# design.net
KiCad netlist of a schematic drawn in Altium Designer
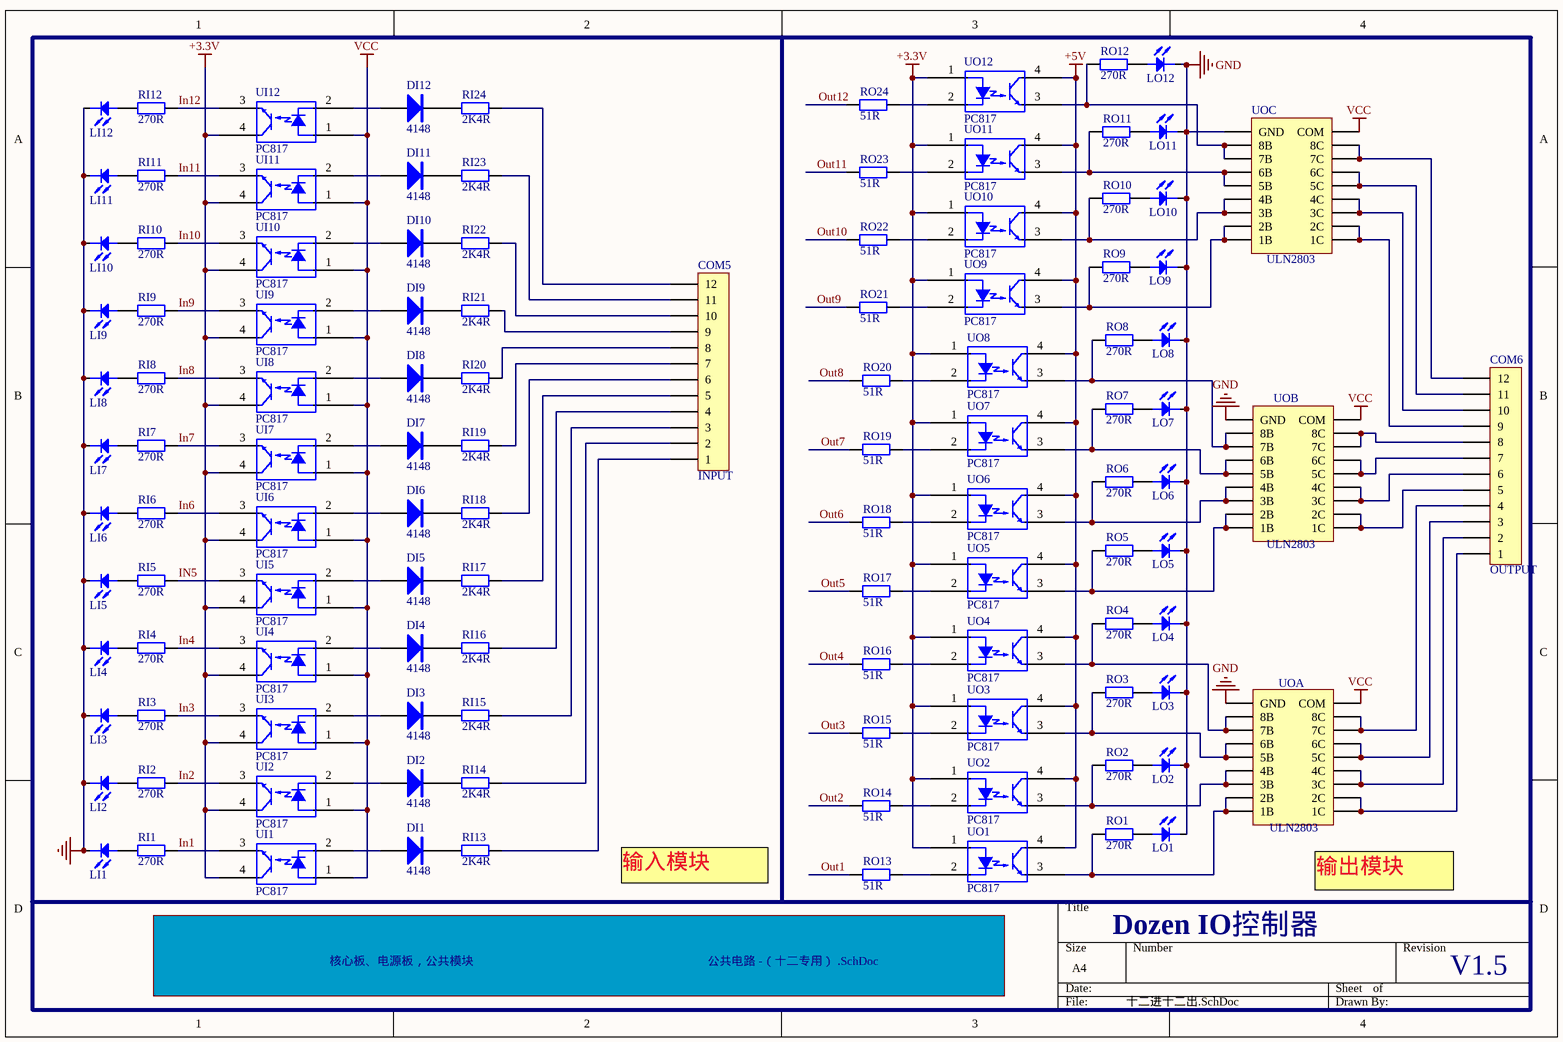
[diagram p0: 十二进十二出.SchDoc]

(export (version "E")
  (design (tool "Eeschema 10.0.6"))
  (components
    (comp (ref "COM5") (value "INPUT") (footprint "CON12-5.1卧上") (libsource (lib "阿波罗") (part "CON12")))
    (comp (ref "COM6") (value "OUTPUT") (footprint "CON12-5.1卧下") (libsource (lib "阿波罗") (part "CON12")))
    (comp (ref "DI1")
      (value "4148")
      (footprint "1206C")
      (libsource (lib "altium-import") (part "root_0__阿波罗.SCHLIB"))
    )
    (comp (ref "DI2")
      (value "4148")
      (footprint "1206C")
      (libsource (lib "altium-import") (part "root_0__阿波罗.SCHLIB"))
    )
    (comp (ref "DI3")
      (value "4148")
      (footprint "1206C")
      (libsource (lib "altium-import") (part "root_0__阿波罗.SCHLIB"))
    )
    (comp (ref "DI4")
      (value "4148")
      (footprint "1206C")
      (libsource (lib "altium-import") (part "root_0__阿波罗.SCHLIB"))
    )
    (comp (ref "DI5")
      (value "4148")
      (footprint "1206C")
      (libsource (lib "altium-import") (part "root_0__阿波罗.SCHLIB"))
    )
    (comp (ref "DI6")
      (value "4148")
      (footprint "1206C")
      (libsource (lib "altium-import") (part "root_0__阿波罗.SCHLIB"))
    )
    (comp (ref "DI7")
      (value "4148")
      (footprint "1206C")
      (libsource (lib "altium-import") (part "root_0__阿波罗.SCHLIB"))
    )
    (comp (ref "DI8")
      (value "4148")
      (footprint "1206C")
      (libsource (lib "altium-import") (part "root_0__阿波罗.SCHLIB"))
    )
    (comp (ref "DI9")
      (value "4148")
      (footprint "1206C")
      (libsource (lib "altium-import") (part "root_0__阿波罗.SCHLIB"))
    )
    (comp (ref "DI10")
      (value "4148")
      (footprint "1206C")
      (libsource (lib "altium-import") (part "root_0__阿波罗.SCHLIB"))
    )
    (comp (ref "DI11")
      (value "4148")
      (footprint "1206C")
      (libsource (lib "altium-import") (part "root_0__阿波罗.SCHLIB"))
    )
    (comp (ref "DI12")
      (value "4148")
      (footprint "1206C")
      (libsource (lib "altium-import") (part "root_0__阿波罗.SCHLIB"))
    )
    (comp (ref "LI1") (value "LED") (footprint "SMDLED") (libsource (lib "*") (part "LED")))
    (comp (ref "LI2") (value "LED") (footprint "SMDLED") (libsource (lib "*") (part "LED")))
    (comp (ref "LI3") (value "LED") (footprint "SMDLED") (libsource (lib "*") (part "LED")))
    (comp (ref "LI4") (value "LED") (footprint "SMDLED") (libsource (lib "*") (part "LED")))
    (comp (ref "LI5") (value "LED") (footprint "SMDLED") (libsource (lib "*") (part "LED")))
    (comp (ref "LI6") (value "LED") (footprint "SMDLED") (libsource (lib "*") (part "LED")))
    (comp (ref "LI7") (value "LED") (footprint "SMDLED") (libsource (lib "*") (part "LED")))
    (comp (ref "LI8") (value "LED") (footprint "SMDLED") (libsource (lib "*") (part "LED")))
    (comp (ref "LI9") (value "LED") (footprint "SMDLED") (libsource (lib "*") (part "LED")))
    (comp (ref "LI10") (value "LED") (footprint "SMDLED") (libsource (lib "*") (part "LED")))
    (comp (ref "LI11") (value "LED") (footprint "SMDLED") (libsource (lib "*") (part "LED")))
    (comp (ref "LI12") (value "LED") (footprint "SMDLED") (libsource (lib "*") (part "LED")))
    (comp (ref "LO1") (value "LED") (footprint "SMDLED") (libsource (lib "*") (part "LED")))
    (comp (ref "LO2") (value "LED") (footprint "SMDLED") (libsource (lib "*") (part "LED")))
    (comp (ref "LO3") (value "LED") (footprint "SMDLED") (libsource (lib "*") (part "LED")))
    (comp (ref "LO4") (value "LED") (footprint "SMDLED") (libsource (lib "*") (part "LED")))
    (comp (ref "LO5") (value "LED") (footprint "SMDLED") (libsource (lib "*") (part "LED")))
    (comp (ref "LO6") (value "LED") (footprint "SMDLED") (libsource (lib "*") (part "LED")))
    (comp (ref "LO7") (value "LED") (footprint "SMDLED") (libsource (lib "*") (part "LED")))
    (comp (ref "LO8") (value "LED") (footprint "SMDLED") (libsource (lib "*") (part "LED")))
    (comp (ref "LO9") (value "LED") (footprint "SMDLED") (libsource (lib "*") (part "LED")))
    (comp (ref "LO10") (value "LED") (footprint "SMDLED") (libsource (lib "*") (part "LED")))
    (comp (ref "LO11") (value "LED") (footprint "SMDLED") (libsource (lib "*") (part "LED")))
    (comp (ref "LO12") (value "LED") (footprint "SMDLED") (libsource (lib "*") (part "LED")))
    (comp (ref "RI1")
      (value "270R")
      (footprint "0603A")
      (description "Resistor")
      (fields (field (name "PUBLISHER") "Altium Limited"))
      (libsource (lib "") (part "Res2_1"))
    )
    (comp (ref "RI2")
      (value "270R")
      (footprint "0603A")
      (description "Resistor")
      (fields (field (name "PUBLISHER") "Altium Limited"))
      (libsource (lib "") (part "Res2_1"))
    )
    (comp (ref "RI3")
      (value "270R")
      (footprint "0603A")
      (description "Resistor")
      (fields (field (name "PUBLISHER") "Altium Limited"))
      (libsource (lib "") (part "Res2_1"))
    )
    (comp (ref "RI4")
      (value "270R")
      (footprint "0603A")
      (description "Resistor")
      (fields (field (name "PUBLISHER") "Altium Limited"))
      (libsource (lib "") (part "Res2_1"))
    )
    (comp (ref "RI5")
      (value "270R")
      (footprint "0603A")
      (description "Resistor")
      (fields (field (name "PUBLISHER") "Altium Limited"))
      (libsource (lib "") (part "Res2_1"))
    )
    (comp (ref "RI6")
      (value "270R")
      (footprint "0603A")
      (description "Resistor")
      (fields (field (name "PUBLISHER") "Altium Limited"))
      (libsource (lib "") (part "Res2_1"))
    )
    (comp (ref "RI7")
      (value "270R")
      (footprint "0603A")
      (description "Resistor")
      (fields (field (name "PUBLISHER") "Altium Limited"))
      (libsource (lib "") (part "Res2_1"))
    )
    (comp (ref "RI8")
      (value "270R")
      (footprint "0603A")
      (description "Resistor")
      (fields (field (name "PUBLISHER") "Altium Limited"))
      (libsource (lib "") (part "Res2_1"))
    )
    (comp (ref "RI9")
      (value "270R")
      (footprint "0603A")
      (description "Resistor")
      (fields (field (name "PUBLISHER") "Altium Limited"))
      (libsource (lib "") (part "Res2_1"))
    )
    (comp (ref "RI10")
      (value "270R")
      (footprint "0603A")
      (description "Resistor")
      (fields (field (name "PUBLISHER") "Altium Limited"))
      (libsource (lib "") (part "Res2_1"))
    )
    (comp (ref "RI11")
      (value "270R")
      (footprint "0603A")
      (description "Resistor")
      (fields (field (name "PUBLISHER") "Altium Limited"))
      (libsource (lib "") (part "Res2_1"))
    )
    (comp (ref "RI12")
      (value "270R")
      (footprint "0603A")
      (description "Resistor")
      (fields (field (name "PUBLISHER") "Altium Limited"))
      (libsource (lib "") (part "Res2_1"))
    )
    (comp (ref "RI13")
      (value "2K4R")
      (footprint "0603A")
      (description "Resistor")
      (fields (field (name "PUBLISHER") "Altium Limited"))
      (libsource (lib "*") (part "Res2"))
    )
    (comp (ref "RI14")
      (value "2K4R")
      (footprint "0603A")
      (description "Resistor")
      (fields (field (name "PUBLISHER") "Altium Limited"))
      (libsource (lib "*") (part "Res2"))
    )
    (comp (ref "RI15")
      (value "2K4R")
      (footprint "0603A")
      (description "Resistor")
      (fields (field (name "PUBLISHER") "Altium Limited"))
      (libsource (lib "*") (part "Res2"))
    )
    (comp (ref "RI16")
      (value "2K4R")
      (footprint "0603A")
      (description "Resistor")
      (fields (field (name "PUBLISHER") "Altium Limited"))
      (libsource (lib "*") (part "Res2"))
    )
    (comp (ref "RI17")
      (value "2K4R")
      (footprint "0603A")
      (description "Resistor")
      (fields (field (name "PUBLISHER") "Altium Limited"))
      (libsource (lib "*") (part "Res2"))
    )
    (comp (ref "RI18")
      (value "2K4R")
      (footprint "0603A")
      (description "Resistor")
      (fields (field (name "PUBLISHER") "Altium Limited"))
      (libsource (lib "*") (part "Res2"))
    )
    (comp (ref "RI19")
      (value "2K4R")
      (footprint "0603A")
      (description "Resistor")
      (fields (field (name "PUBLISHER") "Altium Limited"))
      (libsource (lib "*") (part "Res2"))
    )
    (comp (ref "RI20")
      (value "2K4R")
      (footprint "0603A")
      (description "Resistor")
      (fields (field (name "PUBLISHER") "Altium Limited"))
      (libsource (lib "*") (part "Res2"))
    )
    (comp (ref "RI21")
      (value "2K4R")
      (footprint "0603A")
      (description "Resistor")
      (fields (field (name "PUBLISHER") "Altium Limited"))
      (libsource (lib "*") (part "Res2"))
    )
    (comp (ref "RI22")
      (value "2K4R")
      (footprint "0603A")
      (description "Resistor")
      (fields (field (name "PUBLISHER") "Altium Limited"))
      (libsource (lib "*") (part "Res2"))
    )
    (comp (ref "RI23")
      (value "2K4R")
      (footprint "0603A")
      (description "Resistor")
      (fields (field (name "PUBLISHER") "Altium Limited"))
      (libsource (lib "*") (part "Res2"))
    )
    (comp (ref "RI24")
      (value "2K4R")
      (footprint "0603A")
      (description "Resistor")
      (fields (field (name "PUBLISHER") "Altium Limited"))
      (libsource (lib "*") (part "Res2"))
    )
    (comp (ref "RO1")
      (value "270R")
      (footprint "0603A")
      (description "Resistor")
      (fields (field (name "PUBLISHER") "Altium Limited"))
      (libsource (lib "*") (part "Res2"))
    )
    (comp (ref "RO2")
      (value "270R")
      (footprint "0603A")
      (description "Resistor")
      (fields (field (name "PUBLISHER") "Altium Limited"))
      (libsource (lib "*") (part "Res2"))
    )
    (comp (ref "RO3")
      (value "270R")
      (footprint "0603A")
      (description "Resistor")
      (fields (field (name "PUBLISHER") "Altium Limited"))
      (libsource (lib "*") (part "Res2"))
    )
    (comp (ref "RO4")
      (value "270R")
      (footprint "0603A")
      (description "Resistor")
      (fields (field (name "PUBLISHER") "Altium Limited"))
      (libsource (lib "*") (part "Res2"))
    )
    (comp (ref "RO5")
      (value "270R")
      (footprint "0603A")
      (description "Resistor")
      (fields (field (name "PUBLISHER") "Altium Limited"))
      (libsource (lib "*") (part "Res2"))
    )
    (comp (ref "RO6")
      (value "270R")
      (footprint "0603A")
      (description "Resistor")
      (fields (field (name "PUBLISHER") "Altium Limited"))
      (libsource (lib "*") (part "Res2"))
    )
    (comp (ref "RO7")
      (value "270R")
      (footprint "0603A")
      (description "Resistor")
      (fields (field (name "PUBLISHER") "Altium Limited"))
      (libsource (lib "*") (part "Res2"))
    )
    (comp (ref "RO8")
      (value "270R")
      (footprint "0603A")
      (description "Resistor")
      (fields (field (name "PUBLISHER") "Altium Limited"))
      (libsource (lib "*") (part "Res2"))
    )
    (comp (ref "RO9")
      (value "270R")
      (footprint "0603A")
      (description "Resistor")
      (fields (field (name "PUBLISHER") "Altium Limited"))
      (libsource (lib "*") (part "Res2"))
    )
    (comp (ref "RO10")
      (value "270R")
      (footprint "0603A")
      (description "Resistor")
      (fields (field (name "PUBLISHER") "Altium Limited"))
      (libsource (lib "*") (part "Res2"))
    )
    (comp (ref "RO11")
      (value "270R")
      (footprint "0603A")
      (description "Resistor")
      (fields (field (name "PUBLISHER") "Altium Limited"))
      (libsource (lib "*") (part "Res2"))
    )
    (comp (ref "RO12")
      (value "270R")
      (footprint "0603A")
      (description "Resistor")
      (fields (field (name "PUBLISHER") "Altium Limited"))
      (libsource (lib "*") (part "Res2"))
    )
    (comp (ref "RO13")
      (value "51R")
      (footprint "0603A")
      (description "Resistor")
      (fields (field (name "PUBLISHER") "Altium Limited"))
      (libsource (lib "*") (part "Res2"))
    )
    (comp (ref "RO14")
      (value "51R")
      (footprint "0603A")
      (description "Resistor")
      (fields (field (name "PUBLISHER") "Altium Limited"))
      (libsource (lib "*") (part "Res2"))
    )
    (comp (ref "RO15")
      (value "51R")
      (footprint "0603A")
      (description "Resistor")
      (fields (field (name "PUBLISHER") "Altium Limited"))
      (libsource (lib "*") (part "Res2"))
    )
    (comp (ref "RO16")
      (value "51R")
      (footprint "0603A")
      (description "Resistor")
      (fields (field (name "PUBLISHER") "Altium Limited"))
      (libsource (lib "*") (part "Res2"))
    )
    (comp (ref "RO17")
      (value "51R")
      (footprint "0603A")
      (description "Resistor")
      (fields (field (name "PUBLISHER") "Altium Limited"))
      (libsource (lib "*") (part "Res2"))
    )
    (comp (ref "RO18")
      (value "51R")
      (footprint "0603A")
      (description "Resistor")
      (fields (field (name "PUBLISHER") "Altium Limited"))
      (libsource (lib "*") (part "Res2"))
    )
    (comp (ref "RO19")
      (value "51R")
      (footprint "0603A")
      (description "Resistor")
      (fields (field (name "PUBLISHER") "Altium Limited"))
      (libsource (lib "*") (part "Res2"))
    )
    (comp (ref "RO20")
      (value "51R")
      (footprint "0603A")
      (description "Resistor")
      (fields (field (name "PUBLISHER") "Altium Limited"))
      (libsource (lib "*") (part "Res2"))
    )
    (comp (ref "RO21")
      (value "51R")
      (footprint "0603A")
      (description "Resistor")
      (fields (field (name "PUBLISHER") "Altium Limited"))
      (libsource (lib "*") (part "Res2"))
    )
    (comp (ref "RO22")
      (value "51R")
      (footprint "0603A")
      (description "Resistor")
      (fields (field (name "PUBLISHER") "Altium Limited"))
      (libsource (lib "*") (part "Res2"))
    )
    (comp (ref "RO23")
      (value "51R")
      (footprint "0603A")
      (description "Resistor")
      (fields (field (name "PUBLISHER") "Altium Limited"))
      (libsource (lib "*") (part "Res2"))
    )
    (comp (ref "RO24")
      (value "51R")
      (footprint "0603A")
      (description "Resistor")
      (fields (field (name "PUBLISHER") "Altium Limited"))
      (libsource (lib "*") (part "Res2"))
    )
    (comp (ref "UI1")
      (value "PC817")
      (footprint "PC817")
      (description "Single NPN PhotoTransistor OptoCoupler.")
      (libsource (lib "*") (part "TLP521-1"))
    )
    (comp (ref "UI2")
      (value "PC817")
      (footprint "PC817")
      (description "Single NPN PhotoTransistor OptoCoupler.")
      (libsource (lib "*") (part "TLP521-1"))
    )
    (comp (ref "UI3")
      (value "PC817")
      (footprint "PC817")
      (description "Single NPN PhotoTransistor OptoCoupler.")
      (libsource (lib "*") (part "TLP521-1"))
    )
    (comp (ref "UI4")
      (value "PC817")
      (footprint "PC817")
      (description "Single NPN PhotoTransistor OptoCoupler.")
      (libsource (lib "*") (part "TLP521-1"))
    )
    (comp (ref "UI5")
      (value "PC817")
      (footprint "PC817")
      (description "Single NPN PhotoTransistor OptoCoupler.")
      (libsource (lib "*") (part "TLP521-1"))
    )
    (comp (ref "UI6")
      (value "PC817")
      (footprint "PC817")
      (description "Single NPN PhotoTransistor OptoCoupler.")
      (libsource (lib "*") (part "TLP521-1"))
    )
    (comp (ref "UI7")
      (value "PC817")
      (footprint "PC817")
      (description "Single NPN PhotoTransistor OptoCoupler.")
      (libsource (lib "*") (part "TLP521-1"))
    )
    (comp (ref "UI8")
      (value "PC817")
      (footprint "PC817")
      (description "Single NPN PhotoTransistor OptoCoupler.")
      (libsource (lib "*") (part "TLP521-1"))
    )
    (comp (ref "UI9")
      (value "PC817")
      (footprint "PC817")
      (description "Single NPN PhotoTransistor OptoCoupler.")
      (libsource (lib "*") (part "TLP521-1"))
    )
    (comp (ref "UI10")
      (value "PC817")
      (footprint "PC817")
      (description "Single NPN PhotoTransistor OptoCoupler.")
      (libsource (lib "*") (part "TLP521-1"))
    )
    (comp (ref "UI11")
      (value "PC817")
      (footprint "PC817")
      (description "Single NPN PhotoTransistor OptoCoupler.")
      (libsource (lib "*") (part "TLP521-1"))
    )
    (comp (ref "UI12")
      (value "PC817")
      (footprint "PC817")
      (description "Single NPN PhotoTransistor OptoCoupler.")
      (libsource (lib "*") (part "TLP521-1"))
    )
    (comp (ref "UO1")
      (value "PC817")
      (footprint "PC817")
      (description "Single NPN PhotoTransistor OptoCoupler.")
      (libsource (lib "*") (part "TLP521-1"))
    )
    (comp (ref "UO2")
      (value "PC817")
      (footprint "PC817")
      (description "Single NPN PhotoTransistor OptoCoupler.")
      (libsource (lib "*") (part "TLP521-1"))
    )
    (comp (ref "UO3")
      (value "PC817")
      (footprint "PC817")
      (description "Single NPN PhotoTransistor OptoCoupler.")
      (libsource (lib "*") (part "TLP521-1"))
    )
    (comp (ref "UO4")
      (value "PC817")
      (footprint "PC817")
      (description "Single NPN PhotoTransistor OptoCoupler.")
      (libsource (lib "*") (part "TLP521-1"))
    )
    (comp (ref "UO5")
      (value "PC817")
      (footprint "PC817")
      (description "Single NPN PhotoTransistor OptoCoupler.")
      (libsource (lib "*") (part "TLP521-1"))
    )
    (comp (ref "UO6")
      (value "PC817")
      (footprint "PC817")
      (description "Single NPN PhotoTransistor OptoCoupler.")
      (libsource (lib "*") (part "TLP521-1"))
    )
    (comp (ref "UO7")
      (value "PC817")
      (footprint "PC817")
      (description "Single NPN PhotoTransistor OptoCoupler.")
      (libsource (lib "*") (part "TLP521-1"))
    )
    (comp (ref "UO8")
      (value "PC817")
      (footprint "PC817")
      (description "Single NPN PhotoTransistor OptoCoupler.")
      (libsource (lib "*") (part "TLP521-1"))
    )
    (comp (ref "UO9")
      (value "PC817")
      (footprint "PC817")
      (description "Single NPN PhotoTransistor OptoCoupler.")
      (libsource (lib "*") (part "TLP521-1"))
    )
    (comp (ref "UO10")
      (value "PC817")
      (footprint "PC817")
      (description "Single NPN PhotoTransistor OptoCoupler.")
      (libsource (lib "*") (part "TLP521-1"))
    )
    (comp (ref "UO11")
      (value "PC817")
      (footprint "PC817")
      (description "Single NPN PhotoTransistor OptoCoupler.")
      (libsource (lib "*") (part "TLP521-1"))
    )
    (comp (ref "UO12")
      (value "PC817")
      (footprint "PC817")
      (description "Single NPN PhotoTransistor OptoCoupler.")
      (libsource (lib "*") (part "TLP521-1"))
    )
    (comp (ref "UOA") (value "ULN2803") (footprint "sol18") (libsource (lib "*") (part "ULN2803")))
    (comp (ref "UOB") (value "ULN2803") (footprint "sol18") (libsource (lib "*") (part "ULN2803")))
    (comp (ref "UOC") (value "ULN2803") (footprint "sol18") (libsource (lib "*") (part "ULN2803")))
  )
  (nets
    (net (code "1") (name "+3.3V") (class "Default")
      (node (ref "UI1") (pin "4") (pinfunction "COL_4") (pintype "passive"))
      (node (ref "UI10") (pin "4") (pinfunction "COL_4") (pintype "passive"))
      (node (ref "UI11") (pin "4") (pinfunction "COL_4") (pintype "passive"))
      (node (ref "UI12") (pin "4") (pinfunction "COL_4") (pintype "passive"))
      (node (ref "UI2") (pin "4") (pinfunction "COL_4") (pintype "passive"))
      (node (ref "UI3") (pin "4") (pinfunction "COL_4") (pintype "passive"))
      (node (ref "UI4") (pin "4") (pinfunction "COL_4") (pintype "passive"))
      (node (ref "UI5") (pin "4") (pinfunction "COL_4") (pintype "passive"))
      (node (ref "UI6") (pin "4") (pinfunction "COL_4") (pintype "passive"))
      (node (ref "UI7") (pin "4") (pinfunction "COL_4") (pintype "passive"))
      (node (ref "UI8") (pin "4") (pinfunction "COL_4") (pintype "passive"))
      (node (ref "UI9") (pin "4") (pinfunction "COL_4") (pintype "passive"))
      (node (ref "UO1") (pin "1") (pinfunction "ANODE_1") (pintype "passive"))
      (node (ref "UO10") (pin "1") (pinfunction "ANODE_1") (pintype "passive"))
      (node (ref "UO11") (pin "1") (pinfunction "ANODE_1") (pintype "passive"))
      (node (ref "UO12") (pin "1") (pinfunction "ANODE_1") (pintype "passive"))
      (node (ref "UO2") (pin "1") (pinfunction "ANODE_1") (pintype "passive"))
      (node (ref "UO3") (pin "1") (pinfunction "ANODE_1") (pintype "passive"))
      (node (ref "UO4") (pin "1") (pinfunction "ANODE_1") (pintype "passive"))
      (node (ref "UO5") (pin "1") (pinfunction "ANODE_1") (pintype "passive"))
      (node (ref "UO6") (pin "1") (pinfunction "ANODE_1") (pintype "passive"))
      (node (ref "UO7") (pin "1") (pinfunction "ANODE_1") (pintype "passive"))
      (node (ref "UO8") (pin "1") (pinfunction "ANODE_1") (pintype "passive"))
      (node (ref "UO9") (pin "1") (pinfunction "ANODE_1") (pintype "passive"))
    )
    (net (code "2") (name "+5V") (class "Default")
      (node (ref "UO1") (pin "4") (pinfunction "COL_4") (pintype "passive"))
      (node (ref "UO10") (pin "4") (pinfunction "COL_4") (pintype "passive"))
      (node (ref "UO11") (pin "4") (pinfunction "COL_4") (pintype "passive"))
      (node (ref "UO12") (pin "4") (pinfunction "COL_4") (pintype "passive"))
      (node (ref "UO2") (pin "4") (pinfunction "COL_4") (pintype "passive"))
      (node (ref "UO3") (pin "4") (pinfunction "COL_4") (pintype "passive"))
      (node (ref "UO4") (pin "4") (pinfunction "COL_4") (pintype "passive"))
      (node (ref "UO5") (pin "4") (pinfunction "COL_4") (pintype "passive"))
      (node (ref "UO6") (pin "4") (pinfunction "COL_4") (pintype "passive"))
      (node (ref "UO7") (pin "4") (pinfunction "COL_4") (pintype "passive"))
      (node (ref "UO8") (pin "4") (pinfunction "COL_4") (pintype "passive"))
      (node (ref "UO9") (pin "4") (pinfunction "COL_4") (pintype "passive"))
    )
    (net (code "3") (name "/IN5") (class "Default")
      (node (ref "RI5") (pin "1") (pinfunction "1_1") (pintype "passive"))
      (node (ref "UI5") (pin "3") (pinfunction "EMIT_3") (pintype "passive"))
    )
    (net (code "4") (name "/In1") (class "Default")
      (node (ref "RI1") (pin "1") (pinfunction "1_1") (pintype "passive"))
      (node (ref "UI1") (pin "3") (pinfunction "EMIT_3") (pintype "passive"))
    )
    (net (code "5") (name "/In2") (class "Default")
      (node (ref "RI2") (pin "1") (pinfunction "1_1") (pintype "passive"))
      (node (ref "UI2") (pin "3") (pinfunction "EMIT_3") (pintype "passive"))
    )
    (net (code "6") (name "/In3") (class "Default")
      (node (ref "RI3") (pin "1") (pinfunction "1_1") (pintype "passive"))
      (node (ref "UI3") (pin "3") (pinfunction "EMIT_3") (pintype "passive"))
    )
    (net (code "7") (name "/In4") (class "Default")
      (node (ref "RI4") (pin "1") (pinfunction "1_1") (pintype "passive"))
      (node (ref "UI4") (pin "3") (pinfunction "EMIT_3") (pintype "passive"))
    )
    (net (code "8") (name "/In6") (class "Default")
      (node (ref "RI6") (pin "1") (pinfunction "1_1") (pintype "passive"))
      (node (ref "UI6") (pin "3") (pinfunction "EMIT_3") (pintype "passive"))
    )
    (net (code "9") (name "/In7") (class "Default")
      (node (ref "RI7") (pin "1") (pinfunction "1_1") (pintype "passive"))
      (node (ref "UI7") (pin "3") (pinfunction "EMIT_3") (pintype "passive"))
    )
    (net (code "10") (name "/In8") (class "Default")
      (node (ref "RI8") (pin "1") (pinfunction "1_1") (pintype "passive"))
      (node (ref "UI8") (pin "3") (pinfunction "EMIT_3") (pintype "passive"))
    )
    (net (code "11") (name "/In9") (class "Default")
      (node (ref "RI9") (pin "1") (pinfunction "1_1") (pintype "passive"))
      (node (ref "UI9") (pin "3") (pinfunction "EMIT_3") (pintype "passive"))
    )
    (net (code "12") (name "/In10") (class "Default")
      (node (ref "RI10") (pin "1") (pinfunction "1_1") (pintype "passive"))
      (node (ref "UI10") (pin "3") (pinfunction "EMIT_3") (pintype "passive"))
    )
    (net (code "13") (name "/In11") (class "Default")
      (node (ref "RI11") (pin "1") (pinfunction "1_1") (pintype "passive"))
      (node (ref "UI11") (pin "3") (pinfunction "EMIT_3") (pintype "passive"))
    )
    (net (code "14") (name "/In12") (class "Default")
      (node (ref "RI12") (pin "1") (pinfunction "1_1") (pintype "passive"))
      (node (ref "UI12") (pin "3") (pinfunction "EMIT_3") (pintype "passive"))
    )
    (net (code "15") (name "/Out1") (class "Default")
      (node (ref "RO13") (pin "1") (pinfunction "1_1") (pintype "passive"))
    )
    (net (code "16") (name "/Out2") (class "Default")
      (node (ref "RO14") (pin "1") (pinfunction "1_1") (pintype "passive"))
    )
    (net (code "17") (name "/Out3") (class "Default")
      (node (ref "RO15") (pin "1") (pinfunction "1_1") (pintype "passive"))
    )
    (net (code "18") (name "/Out4") (class "Default")
      (node (ref "RO16") (pin "1") (pinfunction "1_1") (pintype "passive"))
    )
    (net (code "19") (name "/Out5") (class "Default")
      (node (ref "RO17") (pin "1") (pinfunction "1_1") (pintype "passive"))
    )
    (net (code "20") (name "/Out6") (class "Default")
      (node (ref "RO18") (pin "1") (pinfunction "1_1") (pintype "passive"))
    )
    (net (code "21") (name "/Out7") (class "Default")
      (node (ref "RO19") (pin "1") (pinfunction "1_1") (pintype "passive"))
    )
    (net (code "22") (name "/Out8") (class "Default")
      (node (ref "RO20") (pin "1") (pinfunction "1_1") (pintype "passive"))
    )
    (net (code "23") (name "/Out9") (class "Default")
      (node (ref "RO21") (pin "1") (pinfunction "1_1") (pintype "passive"))
    )
    (net (code "24") (name "/Out10") (class "Default")
      (node (ref "RO22") (pin "1") (pinfunction "1_1") (pintype "passive"))
    )
    (net (code "25") (name "/Out11") (class "Default")
      (node (ref "RO23") (pin "1") (pinfunction "1_1") (pintype "passive"))
    )
    (net (code "26") (name "/Out12") (class "Default")
      (node (ref "RO24") (pin "1") (pinfunction "1_1") (pintype "passive"))
    )
    (net (code "27") (name "GND") (class "Default")
      (node (ref "LI1") (pin "K") (pintype "passive"))
      (node (ref "LI10") (pin "K") (pintype "passive"))
      (node (ref "LI11") (pin "K") (pintype "passive"))
      (node (ref "LI12") (pin "K") (pintype "passive"))
      (node (ref "LI2") (pin "K") (pintype "passive"))
      (node (ref "LI3") (pin "K") (pintype "passive"))
      (node (ref "LI4") (pin "K") (pintype "passive"))
      (node (ref "LI5") (pin "K") (pintype "passive"))
      (node (ref "LI6") (pin "K") (pintype "passive"))
      (node (ref "LI7") (pin "K") (pintype "passive"))
      (node (ref "LI8") (pin "K") (pintype "passive"))
      (node (ref "LI9") (pin "K") (pintype "passive"))
      (node (ref "LO1") (pin "K") (pintype "passive"))
      (node (ref "LO10") (pin "K") (pintype "passive"))
      (node (ref "LO11") (pin "K") (pintype "passive"))
      (node (ref "LO12") (pin "K") (pintype "passive"))
      (node (ref "LO2") (pin "K") (pintype "passive"))
      (node (ref "LO3") (pin "K") (pintype "passive"))
      (node (ref "LO4") (pin "K") (pintype "passive"))
      (node (ref "LO5") (pin "K") (pintype "passive"))
      (node (ref "LO6") (pin "K") (pintype "passive"))
      (node (ref "LO7") (pin "K") (pintype "passive"))
      (node (ref "LO8") (pin "K") (pintype "passive"))
      (node (ref "LO9") (pin "K") (pintype "passive"))
      (node (ref "UOA") (pin "9") (pinfunction "GND_9") (pintype "passive"))
      (node (ref "UOB") (pin "9") (pinfunction "GND_9") (pintype "passive"))
      (node (ref "UOC") (pin "9") (pinfunction "GND_9") (pintype "passive"))
    )
    (net (code "28") (name "Net-(COM5-Pad1)") (class "Default")
      (node (ref "COM5") (pin "1") (pinfunction "1_1") (pintype "passive"))
      (node (ref "RI13") (pin "2") (pinfunction "2_2") (pintype "passive"))
    )
    (net (code "29") (name "Net-(COM5-Pad2)") (class "Default")
      (node (ref "COM5") (pin "2") (pinfunction "2_2") (pintype "passive"))
      (node (ref "RI14") (pin "2") (pinfunction "2_2") (pintype "passive"))
    )
    (net (code "30") (name "Net-(COM5-Pad3)") (class "Default")
      (node (ref "COM5") (pin "3") (pinfunction "3_3") (pintype "passive"))
      (node (ref "RI15") (pin "2") (pinfunction "2_2") (pintype "passive"))
    )
    (net (code "31") (name "Net-(COM5-Pad4)") (class "Default")
      (node (ref "COM5") (pin "4") (pinfunction "4_4") (pintype "passive"))
      (node (ref "RI16") (pin "2") (pinfunction "2_2") (pintype "passive"))
    )
    (net (code "32") (name "Net-(COM5-Pad5)") (class "Default")
      (node (ref "COM5") (pin "5") (pinfunction "5_5") (pintype "passive"))
      (node (ref "RI17") (pin "2") (pinfunction "2_2") (pintype "passive"))
    )
    (net (code "33") (name "Net-(COM5-Pad6)") (class "Default")
      (node (ref "COM5") (pin "6") (pinfunction "6_6") (pintype "passive"))
      (node (ref "RI18") (pin "2") (pinfunction "2_2") (pintype "passive"))
    )
    (net (code "34") (name "Net-(COM5-Pad7)") (class "Default")
      (node (ref "COM5") (pin "7") (pinfunction "7_7") (pintype "passive"))
      (node (ref "RI19") (pin "2") (pinfunction "2_2") (pintype "passive"))
    )
    (net (code "35") (name "Net-(COM5-Pad8)") (class "Default")
      (node (ref "COM5") (pin "8") (pinfunction "8_8") (pintype "passive"))
      (node (ref "RI20") (pin "2") (pinfunction "2_2") (pintype "passive"))
    )
    (net (code "36") (name "Net-(COM5-Pad9)") (class "Default")
      (node (ref "COM5") (pin "9") (pinfunction "9_9") (pintype "passive"))
      (node (ref "RI21") (pin "2") (pinfunction "2_2") (pintype "passive"))
    )
    (net (code "37") (name "Net-(COM5-Pad10)") (class "Default")
      (node (ref "COM5") (pin "10") (pinfunction "10_10") (pintype "passive"))
      (node (ref "RI22") (pin "2") (pinfunction "2_2") (pintype "passive"))
    )
    (net (code "38") (name "Net-(COM5-Pad11)") (class "Default")
      (node (ref "COM5") (pin "11") (pinfunction "11_11") (pintype "passive"))
      (node (ref "RI23") (pin "2") (pinfunction "2_2") (pintype "passive"))
    )
    (net (code "39") (name "Net-(COM5-Pad12)") (class "Default")
      (node (ref "COM5") (pin "12") (pinfunction "12_12") (pintype "passive"))
      (node (ref "RI24") (pin "2") (pinfunction "2_2") (pintype "passive"))
    )
    (net (code "40") (name "Net-(DI1-PadK)") (class "Default")
      (node (ref "DI1") (pin "K") (pinfunction "K_K") (pintype "passive"))
      (node (ref "RI13") (pin "1") (pinfunction "1_1") (pintype "passive"))
    )
    (net (code "41") (name "Net-(DI2-PadK)") (class "Default")
      (node (ref "DI2") (pin "K") (pinfunction "K_K") (pintype "passive"))
      (node (ref "RI14") (pin "1") (pinfunction "1_1") (pintype "passive"))
    )
    (net (code "42") (name "Net-(DI3-PadK)") (class "Default")
      (node (ref "DI3") (pin "K") (pinfunction "K_K") (pintype "passive"))
      (node (ref "RI15") (pin "1") (pinfunction "1_1") (pintype "passive"))
    )
    (net (code "43") (name "Net-(DI4-PadK)") (class "Default")
      (node (ref "DI4") (pin "K") (pinfunction "K_K") (pintype "passive"))
      (node (ref "RI16") (pin "1") (pinfunction "1_1") (pintype "passive"))
    )
    (net (code "44") (name "Net-(DI5-PadK)") (class "Default")
      (node (ref "DI5") (pin "K") (pinfunction "K_K") (pintype "passive"))
      (node (ref "RI17") (pin "1") (pinfunction "1_1") (pintype "passive"))
    )
    (net (code "45") (name "Net-(DI6-PadK)") (class "Default")
      (node (ref "DI6") (pin "K") (pinfunction "K_K") (pintype "passive"))
      (node (ref "RI18") (pin "1") (pinfunction "1_1") (pintype "passive"))
    )
    (net (code "46") (name "Net-(DI7-PadK)") (class "Default")
      (node (ref "DI7") (pin "K") (pinfunction "K_K") (pintype "passive"))
      (node (ref "RI19") (pin "1") (pinfunction "1_1") (pintype "passive"))
    )
    (net (code "47") (name "Net-(DI8-PadK)") (class "Default")
      (node (ref "DI8") (pin "K") (pinfunction "K_K") (pintype "passive"))
      (node (ref "RI20") (pin "1") (pinfunction "1_1") (pintype "passive"))
    )
    (net (code "48") (name "Net-(DI9-PadK)") (class "Default")
      (node (ref "DI9") (pin "K") (pinfunction "K_K") (pintype "passive"))
      (node (ref "RI21") (pin "1") (pinfunction "1_1") (pintype "passive"))
    )
    (net (code "49") (name "Net-(DI10-PadK)") (class "Default")
      (node (ref "DI10") (pin "K") (pinfunction "K_K") (pintype "passive"))
      (node (ref "RI22") (pin "1") (pinfunction "1_1") (pintype "passive"))
    )
    (net (code "50") (name "Net-(DI11-PadK)") (class "Default")
      (node (ref "DI11") (pin "K") (pinfunction "K_K") (pintype "passive"))
      (node (ref "RI23") (pin "1") (pinfunction "1_1") (pintype "passive"))
    )
    (net (code "51") (name "Net-(DI12-PadK)") (class "Default")
      (node (ref "DI12") (pin "K") (pinfunction "K_K") (pintype "passive"))
      (node (ref "RI24") (pin "1") (pinfunction "1_1") (pintype "passive"))
    )
    (net (code "52") (name "Net-(LI1-PadA)") (class "Default")
      (node (ref "LI1") (pin "A") (pintype "passive"))
      (node (ref "RI1") (pin "2") (pinfunction "2_2") (pintype "passive"))
    )
    (net (code "53") (name "Net-(LI2-PadA)") (class "Default")
      (node (ref "LI2") (pin "A") (pintype "passive"))
      (node (ref "RI2") (pin "2") (pinfunction "2_2") (pintype "passive"))
    )
    (net (code "54") (name "Net-(LI3-PadA)") (class "Default")
      (node (ref "LI3") (pin "A") (pintype "passive"))
      (node (ref "RI3") (pin "2") (pinfunction "2_2") (pintype "passive"))
    )
    (net (code "55") (name "Net-(LI4-PadA)") (class "Default")
      (node (ref "LI4") (pin "A") (pintype "passive"))
      (node (ref "RI4") (pin "2") (pinfunction "2_2") (pintype "passive"))
    )
    (net (code "56") (name "Net-(LI5-PadA)") (class "Default")
      (node (ref "LI5") (pin "A") (pintype "passive"))
      (node (ref "RI5") (pin "2") (pinfunction "2_2") (pintype "passive"))
    )
    (net (code "57") (name "Net-(LI6-PadA)") (class "Default")
      (node (ref "LI6") (pin "A") (pintype "passive"))
      (node (ref "RI6") (pin "2") (pinfunction "2_2") (pintype "passive"))
    )
    (net (code "58") (name "Net-(LI7-PadA)") (class "Default")
      (node (ref "LI7") (pin "A") (pintype "passive"))
      (node (ref "RI7") (pin "2") (pinfunction "2_2") (pintype "passive"))
    )
    (net (code "59") (name "Net-(LI8-PadA)") (class "Default")
      (node (ref "LI8") (pin "A") (pintype "passive"))
      (node (ref "RI8") (pin "2") (pinfunction "2_2") (pintype "passive"))
    )
    (net (code "60") (name "Net-(LI9-PadA)") (class "Default")
      (node (ref "LI9") (pin "A") (pintype "passive"))
      (node (ref "RI9") (pin "2") (pinfunction "2_2") (pintype "passive"))
    )
    (net (code "61") (name "Net-(LI10-PadA)") (class "Default")
      (node (ref "LI10") (pin "A") (pintype "passive"))
      (node (ref "RI10") (pin "2") (pinfunction "2_2") (pintype "passive"))
    )
    (net (code "62") (name "Net-(LI11-PadA)") (class "Default")
      (node (ref "LI11") (pin "A") (pintype "passive"))
      (node (ref "RI11") (pin "2") (pinfunction "2_2") (pintype "passive"))
    )
    (net (code "63") (name "Net-(LI12-PadA)") (class "Default")
      (node (ref "LI12") (pin "A") (pintype "passive"))
      (node (ref "RI12") (pin "2") (pinfunction "2_2") (pintype "passive"))
    )
    (net (code "64") (name "Net-(LO1-PadA)") (class "Default")
      (node (ref "LO1") (pin "A") (pintype "passive"))
      (node (ref "RO1") (pin "2") (pinfunction "2_2") (pintype "passive"))
    )
    (net (code "65") (name "Net-(LO2-PadA)") (class "Default")
      (node (ref "LO2") (pin "A") (pintype "passive"))
      (node (ref "RO2") (pin "2") (pinfunction "2_2") (pintype "passive"))
    )
    (net (code "66") (name "Net-(LO3-PadA)") (class "Default")
      (node (ref "LO3") (pin "A") (pintype "passive"))
      (node (ref "RO3") (pin "2") (pinfunction "2_2") (pintype "passive"))
    )
    (net (code "67") (name "Net-(LO4-PadA)") (class "Default")
      (node (ref "LO4") (pin "A") (pintype "passive"))
      (node (ref "RO4") (pin "2") (pinfunction "2_2") (pintype "passive"))
    )
    (net (code "68") (name "Net-(LO5-PadA)") (class "Default")
      (node (ref "LO5") (pin "A") (pintype "passive"))
      (node (ref "RO5") (pin "2") (pinfunction "2_2") (pintype "passive"))
    )
    (net (code "69") (name "Net-(LO6-PadA)") (class "Default")
      (node (ref "LO6") (pin "A") (pintype "passive"))
      (node (ref "RO6") (pin "2") (pinfunction "2_2") (pintype "passive"))
    )
    (net (code "70") (name "Net-(LO7-PadA)") (class "Default")
      (node (ref "LO7") (pin "A") (pintype "passive"))
      (node (ref "RO7") (pin "2") (pinfunction "2_2") (pintype "passive"))
    )
    (net (code "71") (name "Net-(LO8-PadA)") (class "Default")
      (node (ref "LO8") (pin "A") (pintype "passive"))
      (node (ref "RO8") (pin "2") (pinfunction "2_2") (pintype "passive"))
    )
    (net (code "72") (name "Net-(LO9-PadA)") (class "Default")
      (node (ref "LO9") (pin "A") (pintype "passive"))
      (node (ref "RO9") (pin "2") (pinfunction "2_2") (pintype "passive"))
    )
    (net (code "73") (name "Net-(LO10-PadA)") (class "Default")
      (node (ref "LO10") (pin "A") (pintype "passive"))
      (node (ref "RO10") (pin "2") (pinfunction "2_2") (pintype "passive"))
    )
    (net (code "74") (name "Net-(LO11-PadA)") (class "Default")
      (node (ref "LO11") (pin "A") (pintype "passive"))
      (node (ref "RO11") (pin "2") (pinfunction "2_2") (pintype "passive"))
    )
    (net (code "75") (name "Net-(LO12-PadA)") (class "Default")
      (node (ref "LO12") (pin "A") (pintype "passive"))
      (node (ref "RO12") (pin "2") (pinfunction "2_2") (pintype "passive"))
    )
    (net (code "76") (name "Net-(UI1-CATH)") (class "Default")
      (node (ref "DI1") (pin "A") (pinfunction "A_A") (pintype "passive"))
      (node (ref "UI1") (pin "2") (pinfunction "CATH_2") (pintype "passive"))
    )
    (net (code "77") (name "Net-(UI2-CATH)") (class "Default")
      (node (ref "DI2") (pin "A") (pinfunction "A_A") (pintype "passive"))
      (node (ref "UI2") (pin "2") (pinfunction "CATH_2") (pintype "passive"))
    )
    (net (code "78") (name "Net-(UI3-CATH)") (class "Default")
      (node (ref "DI3") (pin "A") (pinfunction "A_A") (pintype "passive"))
      (node (ref "UI3") (pin "2") (pinfunction "CATH_2") (pintype "passive"))
    )
    (net (code "79") (name "Net-(UI4-CATH)") (class "Default")
      (node (ref "DI4") (pin "A") (pinfunction "A_A") (pintype "passive"))
      (node (ref "UI4") (pin "2") (pinfunction "CATH_2") (pintype "passive"))
    )
    (net (code "80") (name "Net-(UI5-CATH)") (class "Default")
      (node (ref "DI5") (pin "A") (pinfunction "A_A") (pintype "passive"))
      (node (ref "UI5") (pin "2") (pinfunction "CATH_2") (pintype "passive"))
    )
    (net (code "81") (name "Net-(UI6-CATH)") (class "Default")
      (node (ref "DI6") (pin "A") (pinfunction "A_A") (pintype "passive"))
      (node (ref "UI6") (pin "2") (pinfunction "CATH_2") (pintype "passive"))
    )
    (net (code "82") (name "Net-(UI7-CATH)") (class "Default")
      (node (ref "DI7") (pin "A") (pinfunction "A_A") (pintype "passive"))
      (node (ref "UI7") (pin "2") (pinfunction "CATH_2") (pintype "passive"))
    )
    (net (code "83") (name "Net-(UI8-CATH)") (class "Default")
      (node (ref "DI8") (pin "A") (pinfunction "A_A") (pintype "passive"))
      (node (ref "UI8") (pin "2") (pinfunction "CATH_2") (pintype "passive"))
    )
    (net (code "84") (name "Net-(UI9-CATH)") (class "Default")
      (node (ref "DI9") (pin "A") (pinfunction "A_A") (pintype "passive"))
      (node (ref "UI9") (pin "2") (pinfunction "CATH_2") (pintype "passive"))
    )
    (net (code "85") (name "Net-(UI10-CATH)") (class "Default")
      (node (ref "DI10") (pin "A") (pinfunction "A_A") (pintype "passive"))
      (node (ref "UI10") (pin "2") (pinfunction "CATH_2") (pintype "passive"))
    )
    (net (code "86") (name "Net-(UI11-CATH)") (class "Default")
      (node (ref "DI11") (pin "A") (pinfunction "A_A") (pintype "passive"))
      (node (ref "UI11") (pin "2") (pinfunction "CATH_2") (pintype "passive"))
    )
    (net (code "87") (name "Net-(UI12-CATH)") (class "Default")
      (node (ref "DI12") (pin "A") (pinfunction "A_A") (pintype "passive"))
      (node (ref "UI12") (pin "2") (pinfunction "CATH_2") (pintype "passive"))
    )
    (net (code "88") (name "Net-(UO1-CATH)") (class "Default")
      (node (ref "RO13") (pin "2") (pinfunction "2_2") (pintype "passive"))
      (node (ref "UO1") (pin "2") (pinfunction "CATH_2") (pintype "passive"))
    )
    (net (code "89") (name "Net-(UO1-EMIT)") (class "Default")
      (node (ref "RO1") (pin "1") (pinfunction "1_1") (pintype "passive"))
      (node (ref "UO1") (pin "3") (pinfunction "EMIT_3") (pintype "passive"))
      (node (ref "UOA") (pin "1") (pinfunction "1B_1") (pintype "passive"))
      (node (ref "UOA") (pin "2") (pinfunction "2B_2") (pintype "passive"))
    )
    (net (code "90") (name "Net-(UO2-CATH)") (class "Default")
      (node (ref "RO14") (pin "2") (pinfunction "2_2") (pintype "passive"))
      (node (ref "UO2") (pin "2") (pinfunction "CATH_2") (pintype "passive"))
    )
    (net (code "91") (name "Net-(UO2-EMIT)") (class "Default")
      (node (ref "RO2") (pin "1") (pinfunction "1_1") (pintype "passive"))
      (node (ref "UO2") (pin "3") (pinfunction "EMIT_3") (pintype "passive"))
      (node (ref "UOA") (pin "3") (pinfunction "3B_3") (pintype "passive"))
      (node (ref "UOA") (pin "4") (pinfunction "4B_4") (pintype "passive"))
    )
    (net (code "92") (name "Net-(UO3-CATH)") (class "Default")
      (node (ref "RO15") (pin "2") (pinfunction "2_2") (pintype "passive"))
      (node (ref "UO3") (pin "2") (pinfunction "CATH_2") (pintype "passive"))
    )
    (net (code "93") (name "Net-(UO3-EMIT)") (class "Default")
      (node (ref "RO3") (pin "1") (pinfunction "1_1") (pintype "passive"))
      (node (ref "UO3") (pin "3") (pinfunction "EMIT_3") (pintype "passive"))
      (node (ref "UOA") (pin "5") (pinfunction "5B_5") (pintype "passive"))
      (node (ref "UOA") (pin "6") (pinfunction "6B_6") (pintype "passive"))
    )
    (net (code "94") (name "Net-(UO4-CATH)") (class "Default")
      (node (ref "RO16") (pin "2") (pinfunction "2_2") (pintype "passive"))
      (node (ref "UO4") (pin "2") (pinfunction "CATH_2") (pintype "passive"))
    )
    (net (code "95") (name "Net-(UO4-EMIT)") (class "Default")
      (node (ref "RO4") (pin "1") (pinfunction "1_1") (pintype "passive"))
      (node (ref "UO4") (pin "3") (pinfunction "EMIT_3") (pintype "passive"))
      (node (ref "UOA") (pin "7") (pinfunction "7B_7") (pintype "passive"))
      (node (ref "UOA") (pin "8") (pinfunction "8B_8") (pintype "passive"))
    )
    (net (code "96") (name "Net-(UO5-CATH)") (class "Default")
      (node (ref "RO17") (pin "2") (pinfunction "2_2") (pintype "passive"))
      (node (ref "UO5") (pin "2") (pinfunction "CATH_2") (pintype "passive"))
    )
    (net (code "97") (name "Net-(UO5-EMIT)") (class "Default")
      (node (ref "RO5") (pin "1") (pinfunction "1_1") (pintype "passive"))
      (node (ref "UO5") (pin "3") (pinfunction "EMIT_3") (pintype "passive"))
      (node (ref "UOB") (pin "1") (pinfunction "1B_1") (pintype "passive"))
      (node (ref "UOB") (pin "2") (pinfunction "2B_2") (pintype "passive"))
    )
    (net (code "98") (name "Net-(UO6-CATH)") (class "Default")
      (node (ref "RO18") (pin "2") (pinfunction "2_2") (pintype "passive"))
      (node (ref "UO6") (pin "2") (pinfunction "CATH_2") (pintype "passive"))
    )
    (net (code "99") (name "Net-(UO6-EMIT)") (class "Default")
      (node (ref "RO6") (pin "1") (pinfunction "1_1") (pintype "passive"))
      (node (ref "UO6") (pin "3") (pinfunction "EMIT_3") (pintype "passive"))
      (node (ref "UOB") (pin "3") (pinfunction "3B_3") (pintype "passive"))
      (node (ref "UOB") (pin "4") (pinfunction "4B_4") (pintype "passive"))
    )
    (net (code "100") (name "Net-(UO7-CATH)") (class "Default")
      (node (ref "RO19") (pin "2") (pinfunction "2_2") (pintype "passive"))
      (node (ref "UO7") (pin "2") (pinfunction "CATH_2") (pintype "passive"))
    )
    (net (code "101") (name "Net-(UO7-EMIT)") (class "Default")
      (node (ref "RO7") (pin "1") (pinfunction "1_1") (pintype "passive"))
      (node (ref "UO7") (pin "3") (pinfunction "EMIT_3") (pintype "passive"))
      (node (ref "UOB") (pin "5") (pinfunction "5B_5") (pintype "passive"))
      (node (ref "UOB") (pin "6") (pinfunction "6B_6") (pintype "passive"))
    )
    (net (code "102") (name "Net-(UO8-CATH)") (class "Default")
      (node (ref "RO20") (pin "2") (pinfunction "2_2") (pintype "passive"))
      (node (ref "UO8") (pin "2") (pinfunction "CATH_2") (pintype "passive"))
    )
    (net (code "103") (name "Net-(UO8-EMIT)") (class "Default")
      (node (ref "RO8") (pin "1") (pinfunction "1_1") (pintype "passive"))
      (node (ref "UO8") (pin "3") (pinfunction "EMIT_3") (pintype "passive"))
      (node (ref "UOB") (pin "7") (pinfunction "7B_7") (pintype "passive"))
      (node (ref "UOB") (pin "8") (pinfunction "8B_8") (pintype "passive"))
    )
    (net (code "104") (name "Net-(UO9-CATH)") (class "Default")
      (node (ref "RO21") (pin "2") (pinfunction "2_2") (pintype "passive"))
      (node (ref "UO9") (pin "2") (pinfunction "CATH_2") (pintype "passive"))
    )
    (net (code "105") (name "Net-(UO9-EMIT)") (class "Default")
      (node (ref "RO9") (pin "1") (pinfunction "1_1") (pintype "passive"))
      (node (ref "UO9") (pin "3") (pinfunction "EMIT_3") (pintype "passive"))
      (node (ref "UOC") (pin "1") (pinfunction "1B_1") (pintype "passive"))
      (node (ref "UOC") (pin "2") (pinfunction "2B_2") (pintype "passive"))
    )
    (net (code "106") (name "Net-(UO10-CATH)") (class "Default")
      (node (ref "RO22") (pin "2") (pinfunction "2_2") (pintype "passive"))
      (node (ref "UO10") (pin "2") (pinfunction "CATH_2") (pintype "passive"))
    )
    (net (code "107") (name "Net-(UO10-EMIT)") (class "Default")
      (node (ref "RO10") (pin "1") (pinfunction "1_1") (pintype "passive"))
      (node (ref "UO10") (pin "3") (pinfunction "EMIT_3") (pintype "passive"))
      (node (ref "UOC") (pin "3") (pinfunction "3B_3") (pintype "passive"))
      (node (ref "UOC") (pin "4") (pinfunction "4B_4") (pintype "passive"))
    )
    (net (code "108") (name "Net-(UO11-CATH)") (class "Default")
      (node (ref "RO23") (pin "2") (pinfunction "2_2") (pintype "passive"))
      (node (ref "UO11") (pin "2") (pinfunction "CATH_2") (pintype "passive"))
    )
    (net (code "109") (name "Net-(UO11-EMIT)") (class "Default")
      (node (ref "RO11") (pin "1") (pinfunction "1_1") (pintype "passive"))
      (node (ref "UO11") (pin "3") (pinfunction "EMIT_3") (pintype "passive"))
      (node (ref "UOC") (pin "5") (pinfunction "5B_5") (pintype "passive"))
      (node (ref "UOC") (pin "6") (pinfunction "6B_6") (pintype "passive"))
    )
    (net (code "110") (name "Net-(UO12-CATH)") (class "Default")
      (node (ref "RO24") (pin "2") (pinfunction "2_2") (pintype "passive"))
      (node (ref "UO12") (pin "2") (pinfunction "CATH_2") (pintype "passive"))
    )
    (net (code "111") (name "Net-(UO12-EMIT)") (class "Default")
      (node (ref "RO12") (pin "1") (pinfunction "1_1") (pintype "passive"))
      (node (ref "UO12") (pin "3") (pinfunction "EMIT_3") (pintype "passive"))
      (node (ref "UOC") (pin "7") (pinfunction "7B_7") (pintype "passive"))
      (node (ref "UOC") (pin "8") (pinfunction "8B_8") (pintype "passive"))
    )
    (net (code "112") (name "Net-(UOA-1C)") (class "Default")
      (node (ref "COM6") (pin "1") (pinfunction "1_1") (pintype "passive"))
      (node (ref "UOA") (pin "17") (pinfunction "2C_17") (pintype "passive"))
      (node (ref "UOA") (pin "18") (pinfunction "1C_18") (pintype "passive"))
    )
    (net (code "113") (name "Net-(UOA-3C)") (class "Default")
      (node (ref "COM6") (pin "2") (pinfunction "2_2") (pintype "passive"))
      (node (ref "UOA") (pin "15") (pinfunction "4C_15") (pintype "passive"))
      (node (ref "UOA") (pin "16") (pinfunction "3C_16") (pintype "passive"))
    )
    (net (code "114") (name "Net-(UOA-5C)") (class "Default")
      (node (ref "COM6") (pin "3") (pinfunction "3_3") (pintype "passive"))
      (node (ref "UOA") (pin "13") (pinfunction "6C_13") (pintype "passive"))
      (node (ref "UOA") (pin "14") (pinfunction "5C_14") (pintype "passive"))
    )
    (net (code "115") (name "Net-(UOA-7C)") (class "Default")
      (node (ref "COM6") (pin "4") (pinfunction "4_4") (pintype "passive"))
      (node (ref "UOA") (pin "11") (pinfunction "8C_11") (pintype "passive"))
      (node (ref "UOA") (pin "12") (pinfunction "7C_12") (pintype "passive"))
    )
    (net (code "116") (name "Net-(UOB-1C)") (class "Default")
      (node (ref "COM6") (pin "5") (pinfunction "5_5") (pintype "passive"))
      (node (ref "UOB") (pin "17") (pinfunction "2C_17") (pintype "passive"))
      (node (ref "UOB") (pin "18") (pinfunction "1C_18") (pintype "passive"))
    )
    (net (code "117") (name "Net-(UOB-3C)") (class "Default")
      (node (ref "COM6") (pin "6") (pinfunction "6_6") (pintype "passive"))
      (node (ref "UOB") (pin "15") (pinfunction "4C_15") (pintype "passive"))
      (node (ref "UOB") (pin "16") (pinfunction "3C_16") (pintype "passive"))
    )
    (net (code "118") (name "Net-(UOB-5C)") (class "Default")
      (node (ref "COM6") (pin "7") (pinfunction "7_7") (pintype "passive"))
      (node (ref "UOB") (pin "13") (pinfunction "6C_13") (pintype "passive"))
      (node (ref "UOB") (pin "14") (pinfunction "5C_14") (pintype "passive"))
    )
    (net (code "119") (name "Net-(UOB-7C)") (class "Default")
      (node (ref "COM6") (pin "8") (pinfunction "8_8") (pintype "passive"))
      (node (ref "UOB") (pin "11") (pinfunction "8C_11") (pintype "passive"))
      (node (ref "UOB") (pin "12") (pinfunction "7C_12") (pintype "passive"))
    )
    (net (code "120") (name "Net-(UOC-1C)") (class "Default")
      (node (ref "COM6") (pin "9") (pinfunction "9_9") (pintype "passive"))
      (node (ref "UOC") (pin "17") (pinfunction "2C_17") (pintype "passive"))
      (node (ref "UOC") (pin "18") (pinfunction "1C_18") (pintype "passive"))
    )
    (net (code "121") (name "Net-(UOC-3C)") (class "Default")
      (node (ref "COM6") (pin "10") (pinfunction "10_10") (pintype "passive"))
      (node (ref "UOC") (pin "15") (pinfunction "4C_15") (pintype "passive"))
      (node (ref "UOC") (pin "16") (pinfunction "3C_16") (pintype "passive"))
    )
    (net (code "122") (name "Net-(UOC-5C)") (class "Default")
      (node (ref "COM6") (pin "11") (pinfunction "11_11") (pintype "passive"))
      (node (ref "UOC") (pin "13") (pinfunction "6C_13") (pintype "passive"))
      (node (ref "UOC") (pin "14") (pinfunction "5C_14") (pintype "passive"))
    )
    (net (code "123") (name "Net-(UOC-7C)") (class "Default")
      (node (ref "COM6") (pin "12") (pinfunction "12_12") (pintype "passive"))
      (node (ref "UOC") (pin "11") (pinfunction "8C_11") (pintype "passive"))
      (node (ref "UOC") (pin "12") (pinfunction "7C_12") (pintype "passive"))
    )
    (net (code "124") (name "VCC") (class "Default")
      (node (ref "UI1") (pin "1") (pinfunction "ANODE_1") (pintype "passive"))
      (node (ref "UI10") (pin "1") (pinfunction "ANODE_1") (pintype "passive"))
      (node (ref "UI11") (pin "1") (pinfunction "ANODE_1") (pintype "passive"))
      (node (ref "UI12") (pin "1") (pinfunction "ANODE_1") (pintype "passive"))
      (node (ref "UI2") (pin "1") (pinfunction "ANODE_1") (pintype "passive"))
      (node (ref "UI3") (pin "1") (pinfunction "ANODE_1") (pintype "passive"))
      (node (ref "UI4") (pin "1") (pinfunction "ANODE_1") (pintype "passive"))
      (node (ref "UI5") (pin "1") (pinfunction "ANODE_1") (pintype "passive"))
      (node (ref "UI6") (pin "1") (pinfunction "ANODE_1") (pintype "passive"))
      (node (ref "UI7") (pin "1") (pinfunction "ANODE_1") (pintype "passive"))
      (node (ref "UI8") (pin "1") (pinfunction "ANODE_1") (pintype "passive"))
      (node (ref "UI9") (pin "1") (pinfunction "ANODE_1") (pintype "passive"))
      (node (ref "UOA") (pin "10") (pinfunction "COM_10") (pintype "passive"))
      (node (ref "UOB") (pin "10") (pinfunction "COM_10") (pintype "passive"))
      (node (ref "UOC") (pin "10") (pinfunction "COM_10") (pintype "passive"))
    )
  )
)
